# ASM4003.net
KiCad netlist of a schematic drawn in EAGLE
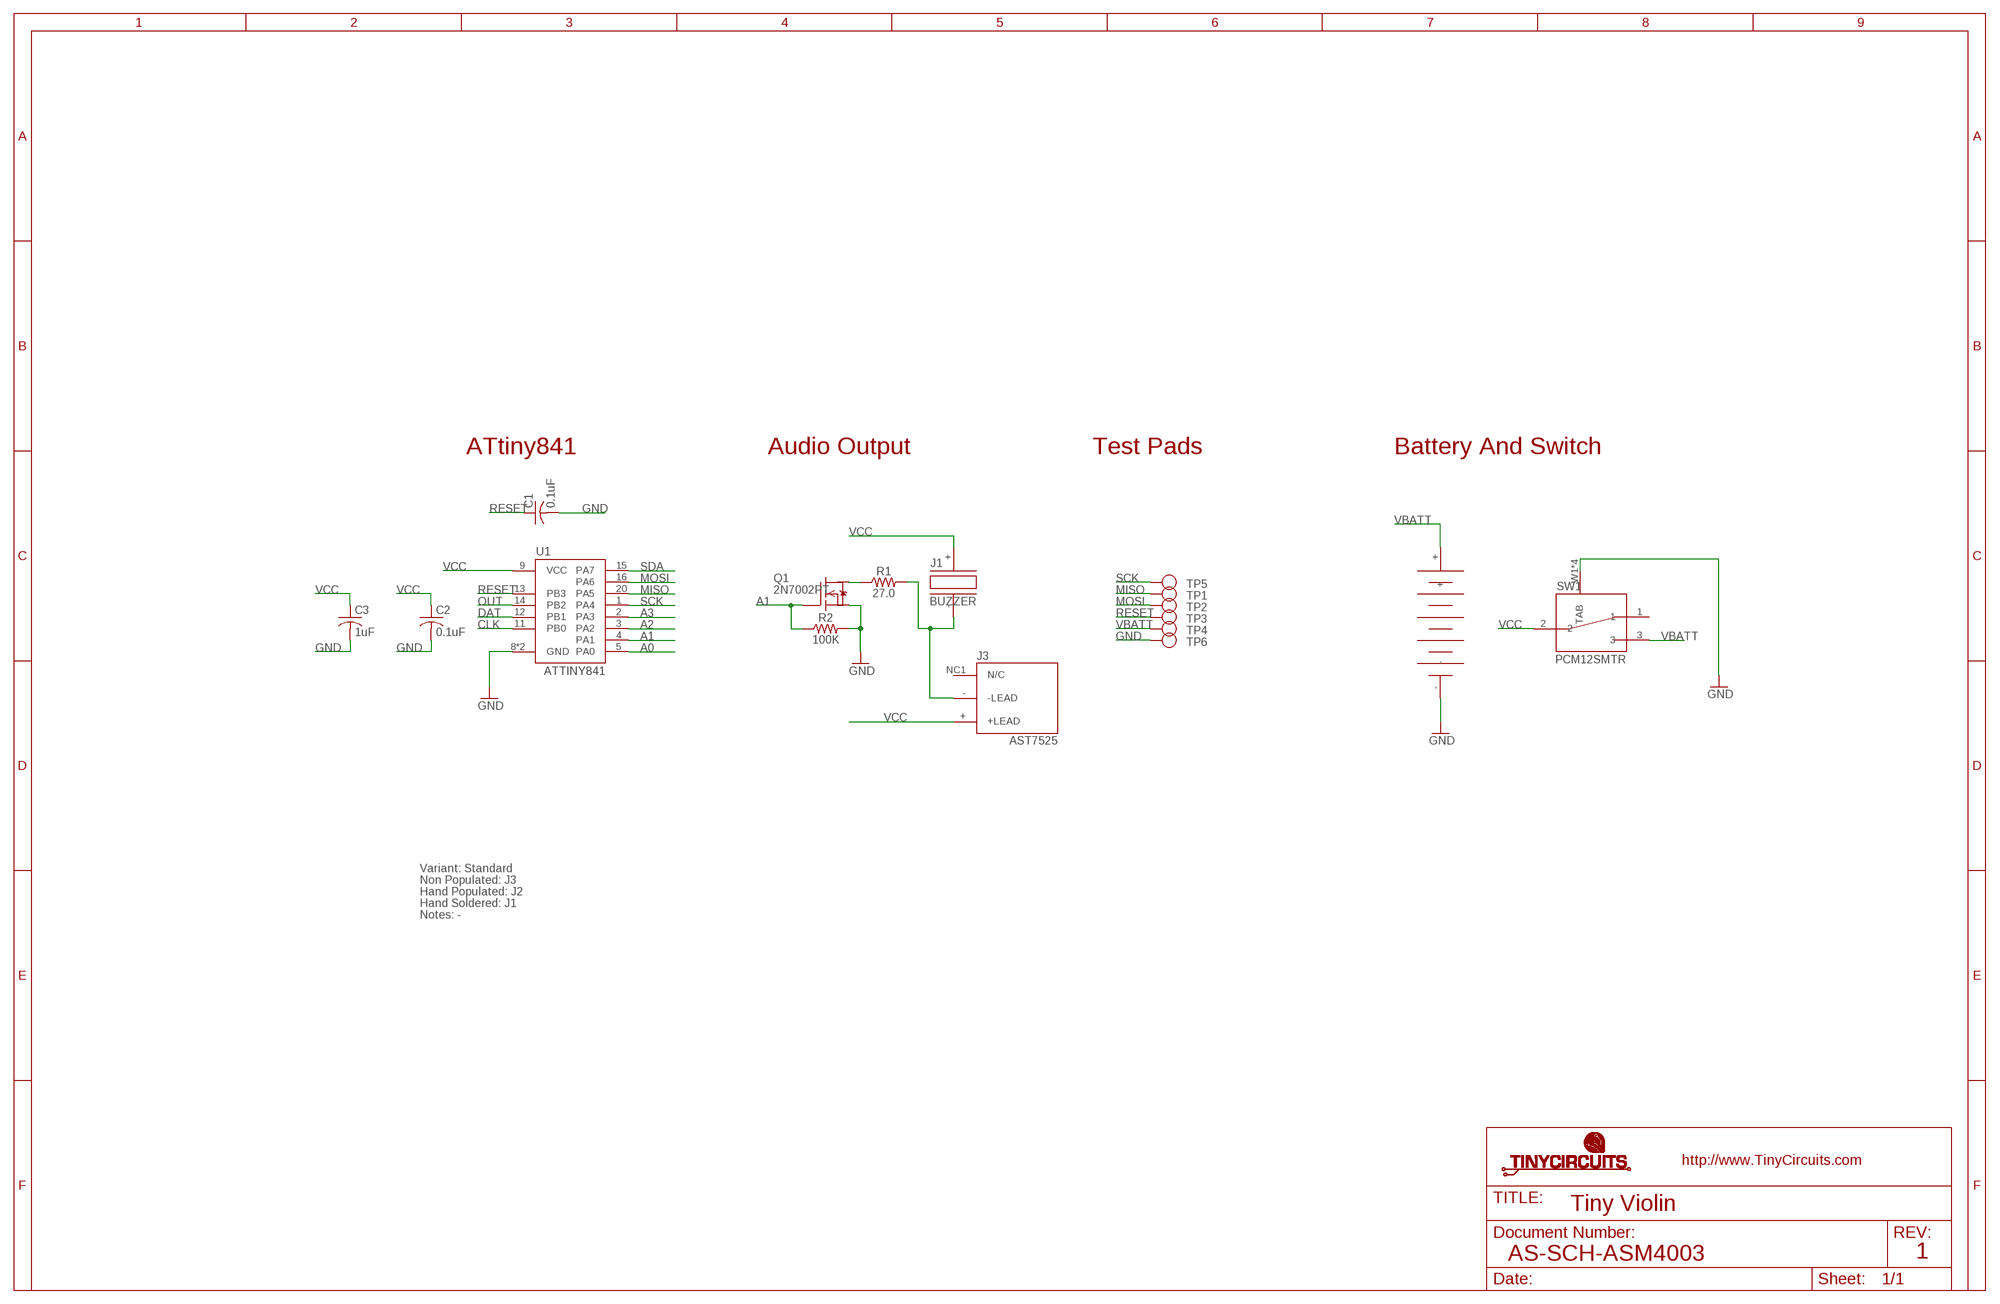
[diagram p0: schematic, sheet 1]

(export (version "E")
  (design (tool "Eeschema 10.0.6"))
  (components
    (comp (ref "C1")
      (value "0.1uF")
      (footprint "eagle-import:C0402")
      (fields (field (name "PARTNO") "AS-ITM-00008") (field (name "PARTNO_1") "AS-ITM-00008"))
      (libsource (lib "eagle-import") (part "AS-ITM-00008"))
    )
    (comp (ref "C2")
      (value "0.1uF")
      (footprint "eagle-import:C0402")
      (fields (field (name "PARTNO") "AS-ITM-00008"))
      (libsource (lib "eagle-import") (part "AS-ITM-00008"))
    )
    (comp (ref "C3")
      (value "1uF")
      (footprint "eagle-import:C0402")
      (fields (field (name "PARTNO") "AS-ITM-00105"))
      (libsource (lib "eagle-import") (part "AS-ITM-00105"))
    )
    (comp (ref "J1")
      (value "BUZZER")
      (footprint "eagle-import:BUZZER_12MM")
      (fields (field (name "PARTNO") "AS-ITM-00440"))
      (libsource (lib "eagle-import") (part "AS-ITM-00440"))
    )
    (comp (ref "J2")
      (value "1225")
      (footprint "eagle-import:COIN_1220_SMD")
      (fields (field (name "PARTNO") "AS-ITM-00468") (field (name "PARTNO_1") "AS-ITM-00468"))
      (libsource (lib "eagle-import") (part "AS-ITM-00468"))
    )
    (comp (ref "J3")
      (value "AST7525")
      (footprint "eagle-import:AST7525")
      (fields (field (name "PARTNO") "AS-ITM-00390"))
      (libsource (lib "eagle-import") (part "AS-ITM-00390"))
    )
    (comp (ref "Q1")
      (value "2N7002PT")
      (footprint "eagle-import:SOT-416")
      (fields (field (name "PARTNO") "AS-ITM-00110"))
      (libsource (lib "eagle-import") (part "AS-ITM-00110"))
    )
    (comp (ref "R1")
      (value "27.0")
      (footprint "eagle-import:0402")
      (fields (field (name "PARTNO") "AS-ITM-00240"))
      (libsource (lib "eagle-import") (part "AS-ITM-00240"))
    )
    (comp (ref "R2")
      (value "100K")
      (footprint "eagle-import:0402")
      (fields (field (name "PARTNO") "AS-ITM-00004"))
      (libsource (lib "eagle-import") (part "AS-ITM-00004"))
    )
    (comp (ref "SW1")
      (value "PCM12SMTR")
      (footprint "eagle-import:PCM12SMTR")
      (fields (field (name "PARTNO") "AS-ITM-00469") (field (name "PARTNO_1") "AS-ITM-00469"))
      (libsource (lib "eagle-import") (part "AS-ITM-00469"))
    )
    (comp (ref "TP1")
      (value "TEST_POINT")
      (footprint "eagle-import:TEST_POINT_1MM")
      (libsource (lib "eagle-import") (part "TEST_POINT"))
    )
    (comp (ref "TP2")
      (value "TEST_POINT")
      (footprint "eagle-import:TEST_POINT_1MM")
      (libsource (lib "eagle-import") (part "TEST_POINT"))
    )
    (comp (ref "TP3")
      (value "TEST_POINT")
      (footprint "eagle-import:TEST_POINT_1MM")
      (libsource (lib "eagle-import") (part "TEST_POINT"))
    )
    (comp (ref "TP4")
      (value "TEST_POINT")
      (footprint "eagle-import:TEST_POINT_1MM")
      (libsource (lib "eagle-import") (part "TEST_POINT"))
    )
    (comp (ref "TP5")
      (value "TEST_POINT")
      (footprint "eagle-import:TEST_POINT_1MM")
      (libsource (lib "eagle-import") (part "TEST_POINT"))
    )
    (comp (ref "TP6")
      (value "TEST_POINT")
      (footprint "eagle-import:TEST_POINT_1MM")
      (libsource (lib "eagle-import") (part "TEST_POINT"))
    )
    (comp (ref "U1")
      (value "ATTINY841")
      (footprint "eagle-import:VQFN-20")
      (fields (field (name "PARTNO") "AS-ITM-00255"))
      (libsource (lib "eagle-import") (part "AS-ITM-00255"))
    )
  )
  (nets
    (net (code "1") (name "/A0") (class "Default")
      (node (ref "U1") (pin "5") (pinfunction "PA0_5") (pintype "bidirectional"))
    )
    (net (code "2") (name "/A1") (class "Default")
      (node (ref "Q1") (pin "1") (pinfunction "G_1") (pintype "passive"))
      (node (ref "R2") (pin "1") (pinfunction "1_1") (pintype "passive"))
      (node (ref "U1") (pin "4") (pinfunction "PA1_4") (pintype "bidirectional"))
    )
    (net (code "3") (name "/A2") (class "Default")
      (node (ref "U1") (pin "3") (pinfunction "PA2_3") (pintype "bidirectional"))
    )
    (net (code "4") (name "/A3") (class "Default")
      (node (ref "U1") (pin "2") (pinfunction "PA3_2") (pintype "bidirectional"))
    )
    (net (code "5") (name "/CLK") (class "Default")
      (node (ref "U1") (pin "11") (pinfunction "PB0_11") (pintype "bidirectional"))
    )
    (net (code "6") (name "/DAT") (class "Default")
      (node (ref "U1") (pin "12") (pinfunction "PB1_12") (pintype "bidirectional"))
    )
    (net (code "7") (name "/MISO") (class "Default")
      (node (ref "TP1") (pin "P$1") (pinfunction "1_P$1") (pintype "bidirectional"))
      (node (ref "U1") (pin "20") (pinfunction "PA5_20") (pintype "bidirectional"))
    )
    (net (code "8") (name "/MOSI") (class "Default")
      (node (ref "TP2") (pin "P$1") (pinfunction "1_P$1") (pintype "bidirectional"))
      (node (ref "U1") (pin "16") (pinfunction "PA6_16") (pintype "bidirectional"))
    )
    (net (code "9") (name "/OUT") (class "Default")
      (node (ref "U1") (pin "14") (pinfunction "PB2_14") (pintype "bidirectional"))
    )
    (net (code "10") (name "/RESET") (class "Default")
      (node (ref "C1") (pin "1") (pinfunction "1_1") (pintype "passive"))
      (node (ref "TP3") (pin "P$1") (pinfunction "1_P$1") (pintype "bidirectional"))
      (node (ref "U1") (pin "13") (pinfunction "PB3_13") (pintype "bidirectional"))
    )
    (net (code "11") (name "/SCK") (class "Default")
      (node (ref "TP5") (pin "P$1") (pinfunction "1_P$1") (pintype "bidirectional"))
      (node (ref "U1") (pin "1") (pinfunction "PA4_1") (pintype "bidirectional"))
    )
    (net (code "12") (name "/SDA") (class "Default")
      (node (ref "U1") (pin "15") (pinfunction "PA7_15") (pintype "bidirectional"))
    )
    (net (code "13") (name "/VBATT") (class "Default")
      (node (ref "J2") (pin "+") (pinfunction "+_+") (pintype "bidirectional"))
      (node (ref "SW1") (pin "3") (pinfunction "3_3") (pintype "bidirectional"))
      (node (ref "TP4") (pin "P$1") (pinfunction "1_P$1") (pintype "bidirectional"))
    )
    (net (code "14") (name "/VCC") (class "Default")
      (node (ref "C2") (pin "1") (pinfunction "1_1") (pintype "passive"))
      (node (ref "C3") (pin "1") (pinfunction "1_1") (pintype "passive"))
      (node (ref "J1") (pin "+") (pinfunction "1_+") (pintype "bidirectional"))
      (node (ref "J3") (pin "+") (pinfunction "+LEAD_+") (pintype "bidirectional"))
      (node (ref "SW1") (pin "2") (pinfunction "2_2") (pintype "bidirectional"))
      (node (ref "U1") (pin "9") (pinfunction "VCC_9") (pintype "bidirectional"))
    )
    (net (code "15") (name "GND") (class "Default")
      (node (ref "C1") (pin "2") (pinfunction "2_2") (pintype "passive"))
      (node (ref "C2") (pin "2") (pinfunction "2_2") (pintype "passive"))
      (node (ref "C3") (pin "2") (pinfunction "2_2") (pintype "passive"))
      (node (ref "J2") (pin "-") (pinfunction "-_-") (pintype "bidirectional"))
      (node (ref "Q1") (pin "2") (pinfunction "S_2") (pintype "passive"))
      (node (ref "R2") (pin "2") (pinfunction "2_2") (pintype "passive"))
      (node (ref "SW1") (pin "W1") (pinfunction "TAB_W1") (pintype "bidirectional"))
      (node (ref "SW1") (pin "W2") (pinfunction "TAB_W2") (pintype "bidirectional"))
      (node (ref "SW1") (pin "W3") (pinfunction "TAB_W3") (pintype "bidirectional"))
      (node (ref "SW1") (pin "W4") (pinfunction "TAB_W4") (pintype "bidirectional"))
      (node (ref "TP6") (pin "P$1") (pinfunction "1_P$1") (pintype "bidirectional"))
      (node (ref "U1") (pin "8") (pinfunction "GND_8") (pintype "bidirectional"))
      (node (ref "U1") (pin "PAD") (pinfunction "GND_PAD") (pintype "bidirectional"))
    )
    (net (code "16") (name "Net-(J1-2)") (class "Default")
      (node (ref "J1") (pin "-") (pinfunction "2_-") (pintype "bidirectional"))
      (node (ref "J3") (pin "-") (pinfunction "-LEAD_-") (pintype "bidirectional"))
      (node (ref "R1") (pin "2") (pinfunction "2_2") (pintype "passive"))
    )
    (net (code "17") (name "Net-(Q1-D)") (class "Default")
      (node (ref "Q1") (pin "3") (pinfunction "D_3") (pintype "passive"))
      (node (ref "R1") (pin "1") (pinfunction "1_1") (pintype "passive"))
    )
    (net (code "18") (name "unconnected-(J3-N{slash}C-PadNC1)") (class "Default")
      (node (ref "J3") (pin "NC1") (pinfunction "N/C_NC1") (pintype "bidirectional"))
    )
    (net (code "19") (name "unconnected-(SW1-Pad1)") (class "Default")
      (node (ref "SW1") (pin "1") (pinfunction "1_1") (pintype "bidirectional"))
    )
  )
)
